# modular-slave.net
KiCad netlist of a schematic drawn in EAGLE
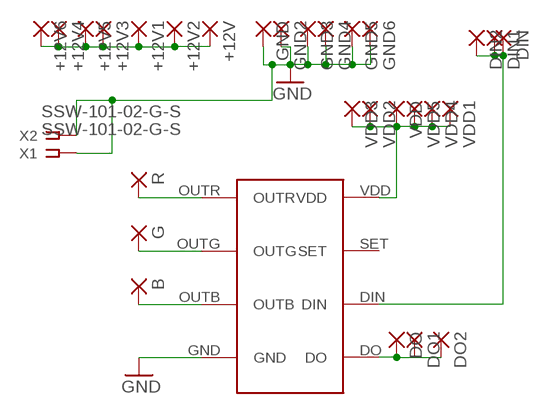
[diagram p0: schematic, sheet 1]

(export (version "E")
  (design (tool "Eeschema 10.0.6"))
  (components
    (comp (ref "+12V")
      (value "SMD5")
      (footprint "eagle-import:SMD2,54-5,08")
      (libsource (lib "eagle-import") (part "SMD5"))
    )
    (comp (ref "+12V1")
      (value "SMD5")
      (footprint "eagle-import:SMD2,54-5,08")
      (libsource (lib "eagle-import") (part "SMD5"))
    )
    (comp (ref "+12V2")
      (value "SMD5")
      (footprint "eagle-import:SMD2,54-5,08")
      (libsource (lib "eagle-import") (part "SMD5"))
    )
    (comp (ref "+12V3")
      (value "SMD5")
      (footprint "eagle-import:SMD2,54-5,08")
      (libsource (lib "eagle-import") (part "SMD5"))
    )
    (comp (ref "+12V4")
      (value "SMD5")
      (footprint "eagle-import:SMD2,54-5,08")
      (libsource (lib "eagle-import") (part "SMD5"))
    )
    (comp (ref "+12V5")
      (value "SMD5")
      (footprint "eagle-import:SMD2,54-5,08")
      (libsource (lib "eagle-import") (part "SMD5"))
    )
    (comp (ref "+12V6")
      (value "SMD5")
      (footprint "eagle-import:SMD2,54-5,08")
      (libsource (lib "eagle-import") (part "SMD5"))
    )
    (comp (ref "0")
      (value "WS2811")
      (footprint "eagle-import:SOP8")
      (libsource (lib "eagle-import") (part "WS2811"))
    )
    (comp (ref "B")
      (value "SMD5")
      (footprint "eagle-import:SMD2,54-5,08")
      (libsource (lib "eagle-import") (part "SMD5"))
    )
    (comp (ref "DIN")
      (value "SMD5")
      (footprint "eagle-import:SMD2,54-5,08")
      (libsource (lib "eagle-import") (part "SMD5"))
    )
    (comp (ref "DIN1")
      (value "SMD5")
      (footprint "eagle-import:SMD2,54-5,08")
      (libsource (lib "eagle-import") (part "SMD5"))
    )
    (comp (ref "DIN2")
      (value "SMD5")
      (footprint "eagle-import:SMD2,54-5,08")
      (libsource (lib "eagle-import") (part "SMD5"))
    )
    (comp (ref "DO")
      (value "SMD5")
      (footprint "eagle-import:SMD2,54-5,08")
      (libsource (lib "eagle-import") (part "SMD5"))
    )
    (comp (ref "DO1")
      (value "SMD5")
      (footprint "eagle-import:SMD2,54-5,08")
      (libsource (lib "eagle-import") (part "SMD5"))
    )
    (comp (ref "DO2")
      (value "SMD5")
      (footprint "eagle-import:SMD2,54-5,08")
      (libsource (lib "eagle-import") (part "SMD5"))
    )
    (comp (ref "G")
      (value "SMD5")
      (footprint "eagle-import:SMD2,54-5,08")
      (libsource (lib "eagle-import") (part "SMD5"))
    )
    (comp (ref "GND")
      (value "SMD5")
      (footprint "eagle-import:SMD2,54-5,08")
      (libsource (lib "eagle-import") (part "SMD5"))
    )
    (comp (ref "GND2")
      (value "SMD5")
      (footprint "eagle-import:SMD2,54-5,08")
      (libsource (lib "eagle-import") (part "SMD5"))
    )
    (comp (ref "GND3")
      (value "SMD5")
      (footprint "eagle-import:SMD2,54-5,08")
      (libsource (lib "eagle-import") (part "SMD5"))
    )
    (comp (ref "GND4")
      (value "SMD5")
      (footprint "eagle-import:SMD2,54-5,08")
      (libsource (lib "eagle-import") (part "SMD5"))
    )
    (comp (ref "GND5")
      (value "SMD5")
      (footprint "eagle-import:SMD2,54-5,08")
      (libsource (lib "eagle-import") (part "SMD5"))
    )
    (comp (ref "GND6")
      (value "SMD5")
      (footprint "eagle-import:SMD2,54-5,08")
      (libsource (lib "eagle-import") (part "SMD5"))
    )
    (comp (ref "R")
      (value "SMD5")
      (footprint "eagle-import:SMD2,54-5,08")
      (libsource (lib "eagle-import") (part "SMD5"))
    )
    (comp (ref "VDD")
      (value "SMD5")
      (footprint "eagle-import:SMD2,54-5,08")
      (libsource (lib "eagle-import") (part "SMD5"))
    )
    (comp (ref "VDD1")
      (value "SMD5")
      (footprint "eagle-import:SMD2,54-5,08")
      (libsource (lib "eagle-import") (part "SMD5"))
    )
    (comp (ref "VDD2")
      (value "SMD5")
      (footprint "eagle-import:SMD2,54-5,08")
      (libsource (lib "eagle-import") (part "SMD5"))
    )
    (comp (ref "VDD3")
      (value "SMD5")
      (footprint "eagle-import:SMD2,54-5,08")
      (libsource (lib "eagle-import") (part "SMD5"))
    )
    (comp (ref "VDD4")
      (value "SMD5")
      (footprint "eagle-import:SMD2,54-5,08")
      (libsource (lib "eagle-import") (part "SMD5"))
    )
    (comp (ref "VDD5")
      (value "SMD5")
      (footprint "eagle-import:SMD2,54-5,08")
      (libsource (lib "eagle-import") (part "SMD5"))
    )
    (comp (ref "X1")
      (value "SSW-101-02-G-S")
      (footprint "eagle-import:SSW-101-02-G-S")
      (fields (field (name "MF") "Samtec Inc."))
      (libsource (lib "eagle-import") (part "SSW-101-02-G-S"))
    )
    (comp (ref "X2")
      (value "SSW-101-02-G-S")
      (footprint "eagle-import:SSW-101-02-G-S")
      (fields (field (name "MF") "Samtec Inc."))
      (libsource (lib "eagle-import") (part "SSW-101-02-G-S"))
    )
  )
  (nets
    (net (code "1") (name "GND") (class "Default")
      (node (ref "0") (pin "GND") (pinfunction "GND_GND") (pintype "bidirectional"))
      (node (ref "GND") (pin "1") (pinfunction "P_1") (pintype "passive"))
      (node (ref "GND2") (pin "1") (pinfunction "P_1") (pintype "passive"))
      (node (ref "GND3") (pin "1") (pinfunction "P_1") (pintype "passive"))
      (node (ref "GND4") (pin "1") (pinfunction "P_1") (pintype "passive"))
      (node (ref "GND5") (pin "1") (pinfunction "P_1") (pintype "passive"))
      (node (ref "GND6") (pin "1") (pinfunction "P_1") (pintype "passive"))
      (node (ref "X1") (pin "1") (pinfunction "1_1") (pintype "passive"))
      (node (ref "X2") (pin "1") (pinfunction "1_1") (pintype "passive"))
    )
    (net (code "2") (name "Net-(+12V-P)") (class "Default")
      (node (ref "+12V") (pin "1") (pinfunction "P_1") (pintype "passive"))
      (node (ref "+12V1") (pin "1") (pinfunction "P_1") (pintype "passive"))
      (node (ref "+12V2") (pin "1") (pinfunction "P_1") (pintype "passive"))
      (node (ref "+12V3") (pin "1") (pinfunction "P_1") (pintype "passive"))
      (node (ref "+12V4") (pin "1") (pinfunction "P_1") (pintype "passive"))
      (node (ref "+12V5") (pin "1") (pinfunction "P_1") (pintype "passive"))
      (node (ref "+12V6") (pin "1") (pinfunction "P_1") (pintype "passive"))
    )
    (net (code "3") (name "Net-(B-P)") (class "Default")
      (node (ref "0") (pin "OUTB") (pinfunction "OUTB_OUTB") (pintype "bidirectional"))
      (node (ref "B") (pin "1") (pinfunction "P_1") (pintype "passive"))
    )
    (net (code "4") (name "Net-(DIN-P)") (class "Default")
      (node (ref "0") (pin "DIN") (pinfunction "DIN_DIN") (pintype "bidirectional"))
      (node (ref "DIN") (pin "1") (pinfunction "P_1") (pintype "passive"))
      (node (ref "DIN1") (pin "1") (pinfunction "P_1") (pintype "passive"))
      (node (ref "DIN2") (pin "1") (pinfunction "P_1") (pintype "passive"))
    )
    (net (code "5") (name "Net-(DO-P)") (class "Default")
      (node (ref "0") (pin "DO") (pinfunction "DO_DO") (pintype "bidirectional"))
      (node (ref "DO") (pin "1") (pinfunction "P_1") (pintype "passive"))
      (node (ref "DO1") (pin "1") (pinfunction "P_1") (pintype "passive"))
      (node (ref "DO2") (pin "1") (pinfunction "P_1") (pintype "passive"))
    )
    (net (code "6") (name "Net-(G-P)") (class "Default")
      (node (ref "0") (pin "OUTG") (pinfunction "OUTG_OUTG") (pintype "bidirectional"))
      (node (ref "G") (pin "1") (pinfunction "P_1") (pintype "passive"))
    )
    (net (code "7") (name "Net-(R-P)") (class "Default")
      (node (ref "0") (pin "OUTR") (pinfunction "OUTR_OUTR") (pintype "bidirectional"))
      (node (ref "R") (pin "1") (pinfunction "P_1") (pintype "passive"))
    )
    (net (code "8") (name "Net-(VDD-P)") (class "Default")
      (node (ref "0") (pin "VDD") (pinfunction "VDD_VDD") (pintype "bidirectional"))
      (node (ref "VDD") (pin "1") (pinfunction "P_1") (pintype "passive"))
      (node (ref "VDD1") (pin "1") (pinfunction "P_1") (pintype "passive"))
      (node (ref "VDD2") (pin "1") (pinfunction "P_1") (pintype "passive"))
      (node (ref "VDD3") (pin "1") (pinfunction "P_1") (pintype "passive"))
      (node (ref "VDD4") (pin "1") (pinfunction "P_1") (pintype "passive"))
      (node (ref "VDD5") (pin "1") (pinfunction "P_1") (pintype "passive"))
    )
    (net (code "9") (name "unconnected-(0-PadSET)") (class "Default")
      (node (ref "0") (pin "SET") (pinfunction "SET_SET") (pintype "bidirectional"))
    )
  )
)
